# Main.net
KiCad netlist of a schematic drawn in Altium Designer
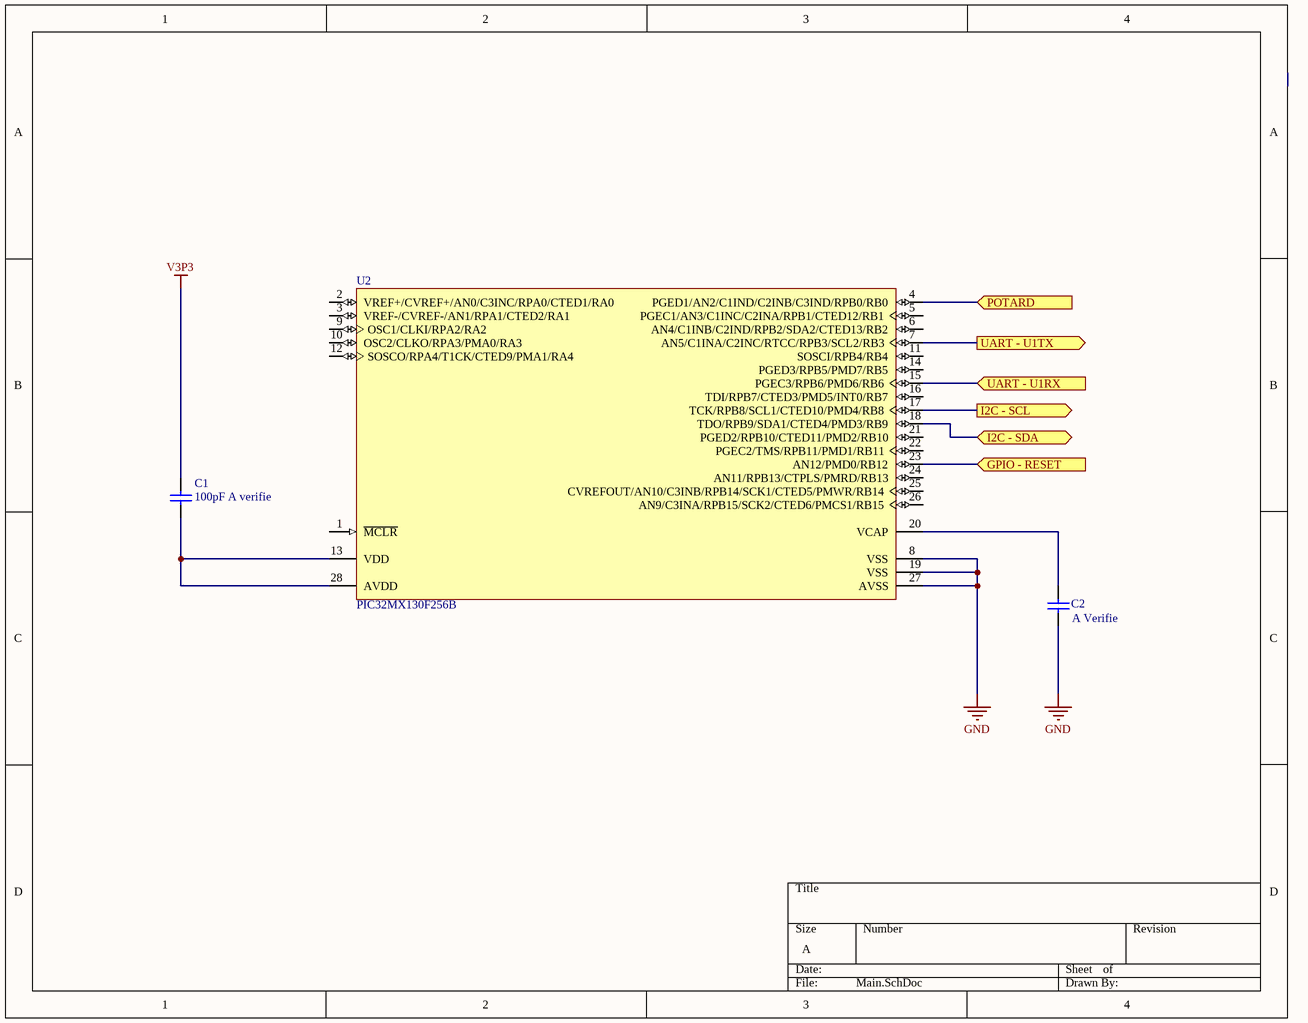
[diagram p0: Main.SchDoc]

(export (version "E")
  (design (tool "Eeschema 10.0.6"))
  (components
    (comp (ref "C1")
      (value "100pF A verifie")
      (footprint "CAP 0603")
      (description "Capacitor")
      (fields (field (name "Comment") "Cap") (field (name "PUBLISHER") "Altium Limited"))
      (libsource (lib "Miscellaneous Devices") (part "Cap"))
    )
    (comp (ref "C2")
      (value "A Verifie")
      (footprint "CAP 0603")
      (description "Capacitor")
      (fields (field (name "Comment") "Cap") (field (name "PUBLISHER") "Altium Limited"))
      (libsource (lib "Miscellaneous Devices") (part "Cap"))
    )
    (comp (ref "U2")
      (value "PIC32MX130F256B")
      (footprint "PIC32MX130F256B")
      (description "PIC32MX Family Microcontroller")
      (libsource (lib "Schematics_Library") (part "PIC32MX130F256B"))
    )
  )
  (nets
    (net (code "1") (name "/GPIO - RESET") (class "Default")
      (node (ref "U2") (pin "23") (pinfunction "AN12/PMD0/RB12_23") (pintype "bidirectional"))
    )
    (net (code "2") (name "/I2C - SCL") (class "Default")
      (node (ref "U2") (pin "17") (pinfunction "TCK/RPB8/SCL1/CTED10/PMD4/RB8_17") (pintype "bidirectional"))
    )
    (net (code "3") (name "/I2C - SDA") (class "Default")
      (node (ref "U2") (pin "18") (pinfunction "TDO/RPB9/SDA1/CTED4/PMD3/RB9_18") (pintype "bidirectional"))
    )
    (net (code "4") (name "/POTARD") (class "Default")
      (node (ref "U2") (pin "4") (pinfunction "PGED1/AN2/C1IND/C2INB/C3IND/RPB0/RB0_4") (pintype "bidirectional"))
    )
    (net (code "5") (name "/UART - U1RX") (class "Default")
      (node (ref "U2") (pin "15") (pinfunction "PGEC3/RPB6/PMD6/RB6_15") (pintype "bidirectional"))
    )
    (net (code "6") (name "/UART - U1TX") (class "Default")
      (node (ref "U2") (pin "7") (pinfunction "AN5/C1INA/C2INC/RTCC/RPB3/SCL2/RB3_7") (pintype "bidirectional"))
    )
    (net (code "7") (name "GND") (class "Default")
      (node (ref "C2") (pin "1") (pinfunction "1_1") (pintype "passive"))
      (node (ref "U2") (pin "19") (pinfunction "VSS_19") (pintype "power_in"))
      (node (ref "U2") (pin "27") (pinfunction "AVSS_27") (pintype "power_in"))
      (node (ref "U2") (pin "8") (pinfunction "VSS_8") (pintype "power_in"))
    )
    (net (code "8") (name "Net-(U2-AVDD)") (class "Default")
      (node (ref "C1") (pin "1") (pinfunction "1_1") (pintype "passive"))
      (node (ref "U2") (pin "13") (pinfunction "VDD_13") (pintype "power_in"))
      (node (ref "U2") (pin "28") (pinfunction "AVDD_28") (pintype "power_in"))
    )
    (net (code "9") (name "Net-(U2-VCAP)") (class "Default")
      (node (ref "C2") (pin "2") (pinfunction "2_2") (pintype "passive"))
      (node (ref "U2") (pin "20") (pinfunction "VCAP_20") (pintype "passive"))
    )
    (net (code "10") (name "V3P3") (class "Default")
      (node (ref "C1") (pin "2") (pinfunction "2_2") (pintype "passive"))
    )
    (net (code "11") (name "unconnected-(U2-AN4{slash}C1INB{slash}C2IND{slash}RPB2{slash}SDA2{slash}CTED13{slash}RB2-Pad6)") (class "Default")
      (node (ref "U2") (pin "6") (pinfunction "AN4/C1INB/C2IND/RPB2/SDA2/CTED13/RB2_6") (pintype "bidirectional"))
    )
    (net (code "12") (name "unconnected-(U2-AN9{slash}C3INA{slash}RPB15{slash}SCK2{slash}CTED6{slash}PMCS1{slash}RB15-Pad26)") (class "Default")
      (node (ref "U2") (pin "26") (pinfunction "AN9/C3INA/RPB15/SCK2/CTED6/PMCS1/RB15_26") (pintype "bidirectional"))
    )
    (net (code "13") (name "unconnected-(U2-AN11{slash}RPB13{slash}CTPLS{slash}PMRD{slash}RB13-Pad24)") (class "Default")
      (node (ref "U2") (pin "24") (pinfunction "AN11/RPB13/CTPLS/PMRD/RB13_24") (pintype "bidirectional"))
    )
    (net (code "14") (name "unconnected-(U2-CVREFOUT{slash}AN10{slash}C3INB{slash}RPB14{slash}SCK1{slash}CTED5{slash}PMWR{slash}RB14-Pad25)") (class "Default")
      (node (ref "U2") (pin "25") (pinfunction "CVREFOUT/AN10/C3INB/RPB14/SCK1/CTED5/PMWR/RB14_25") (pintype "bidirectional"))
    )
    (net (code "15") (name "unconnected-(U2-OSC1{slash}CLKI{slash}RPA2{slash}RA2-Pad9)") (class "Default")
      (node (ref "U2") (pin "9") (pinfunction "OSC1/CLKI/RPA2/RA2_9") (pintype "bidirectional"))
    )
    (net (code "16") (name "unconnected-(U2-OSC2{slash}CLKO{slash}RPA3{slash}PMA0{slash}RA3-Pad10)") (class "Default")
      (node (ref "U2") (pin "10") (pinfunction "OSC2/CLKO/RPA3/PMA0/RA3_10") (pintype "bidirectional"))
    )
    (net (code "17") (name "unconnected-(U2-PGEC1{slash}AN3{slash}C1INC{slash}C2INA{slash}RPB1{slash}CTED12{slash}RB1-Pad5)") (class "Default")
      (node (ref "U2") (pin "5") (pinfunction "PGEC1/AN3/C1INC/C2INA/RPB1/CTED12/RB1_5") (pintype "bidirectional"))
    )
    (net (code "18") (name "unconnected-(U2-PGEC2{slash}TMS{slash}RPB11{slash}PMD1{slash}RB11-Pad22)") (class "Default")
      (node (ref "U2") (pin "22") (pinfunction "PGEC2/TMS/RPB11/PMD1/RB11_22") (pintype "bidirectional"))
    )
    (net (code "19") (name "unconnected-(U2-PGED2{slash}RPB10{slash}CTED11{slash}PMD2{slash}RB10-Pad21)") (class "Default")
      (node (ref "U2") (pin "21") (pinfunction "PGED2/RPB10/CTED11/PMD2/RB10_21") (pintype "bidirectional"))
    )
    (net (code "20") (name "unconnected-(U2-PGED3{slash}RPB5{slash}PMD7{slash}RB5-Pad14)") (class "Default")
      (node (ref "U2") (pin "14") (pinfunction "PGED3/RPB5/PMD7/RB5_14") (pintype "bidirectional"))
    )
    (net (code "21") (name "unconnected-(U2-SOSCI{slash}RPB4{slash}RB4-Pad11)") (class "Default")
      (node (ref "U2") (pin "11") (pinfunction "SOSCI/RPB4/RB4_11") (pintype "bidirectional"))
    )
    (net (code "22") (name "unconnected-(U2-SOSCO{slash}RPA4{slash}T1CK{slash}CTED9{slash}PMA1{slash}RA4-Pad12)") (class "Default")
      (node (ref "U2") (pin "12") (pinfunction "SOSCO/RPA4/T1CK/CTED9/PMA1/RA4_12") (pintype "bidirectional"))
    )
    (net (code "23") (name "unconnected-(U2-TDI{slash}RPB7{slash}CTED3{slash}PMD5{slash}INT0{slash}RB7-Pad16)") (class "Default")
      (node (ref "U2") (pin "16") (pinfunction "TDI/RPB7/CTED3/PMD5/INT0/RB7_16") (pintype "bidirectional"))
    )
    (net (code "24") (name "unconnected-(U2-VREF+{slash}CVREF+{slash}AN0{slash}C3INC{slash}RPA0{slash}CTED1{slash}RA0-Pad2)") (class "Default")
      (node (ref "U2") (pin "2") (pinfunction "VREF+/CVREF+/AN0/C3INC/RPA0/CTED1/RA0_2") (pintype "bidirectional"))
    )
    (net (code "25") (name "unconnected-(U2-VREF-{slash}CVREF-{slash}AN1{slash}RPA1{slash}CTED2{slash}RA1-Pad3)") (class "Default")
      (node (ref "U2") (pin "3") (pinfunction "VREF-/CVREF-/AN1/RPA1/CTED2/RA1_3") (pintype "bidirectional"))
    )
    (net (code "26") (name "unconnected-(U2-~{MCLR}-Pad1)") (class "Default")
      (node (ref "U2") (pin "1") (pinfunction "~{MCLR}_1") (pintype "input"))
    )
  )
)
